# fixie18.net
KiCad netlist of a schematic drawn in EAGLE
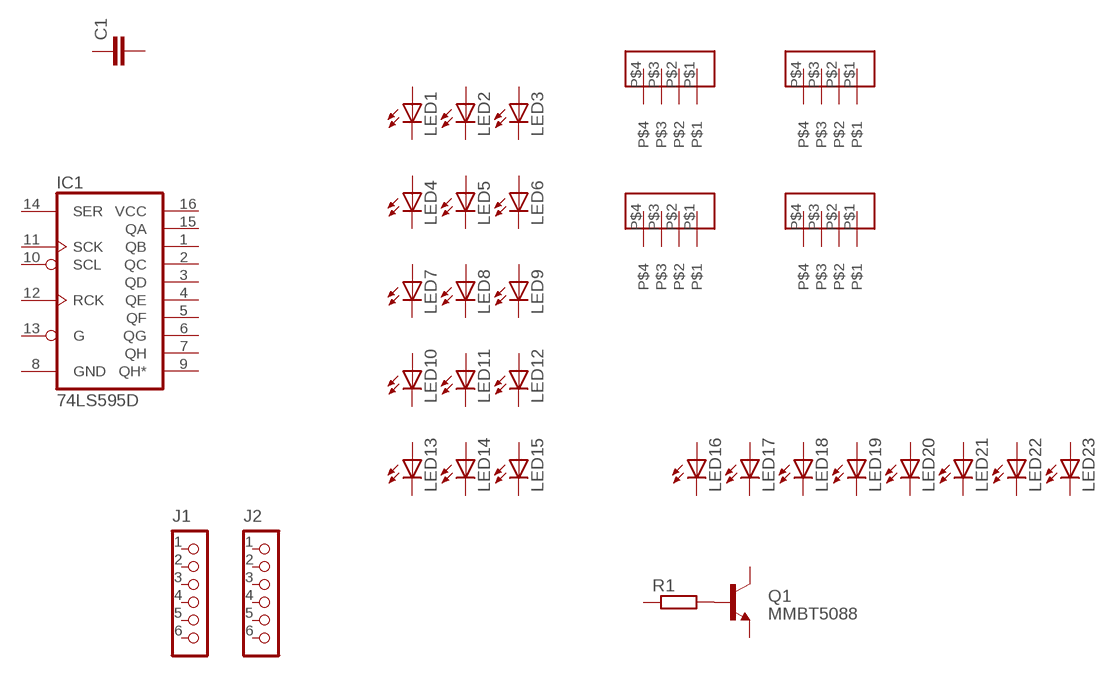
[diagram p0: schematic, sheet 1]

(export (version "E")
  (design (tool "Eeschema 10.0.6"))
  (components
    (comp (ref "C1")
      (value "C-EUC1206")
      (footprint "eagle-import:C1206")
      (libsource (lib "eagle-import") (part "C-EUC1206"))
    )
    (comp (ref "IC1")
      (value "74LS595D")
      (footprint "eagle-import:SO16")
      (libsource (lib "eagle-import") (part "74595DLS"))
    )
    (comp (ref "J1")
      (value "CON_HEADER_1X06-PTH")
      (footprint "eagle-import:M1X6")
      (libsource (lib "eagle-import") (part "CON_HEADER_1X06-PTH"))
    )
    (comp (ref "J2")
      (value "CON_HEADER_1X06-PTH")
      (footprint "eagle-import:M1X6")
      (libsource (lib "eagle-import") (part "CON_HEADER_1X06-PTH"))
    )
    (comp (ref "JP1")
      (value "HEADER_CENTERED_04")
      (footprint "eagle-import:HEADER_04_CENTERED")
      (libsource (lib "eagle-import") (part "HEADER_CENTERED_04"))
    )
    (comp (ref "JP2")
      (value "HEADER_CENTERED_04")
      (footprint "eagle-import:HEADER_04_CENTERED")
      (libsource (lib "eagle-import") (part "HEADER_CENTERED_04"))
    )
    (comp (ref "JP3")
      (value "HEADER_CENTERED_04")
      (footprint "eagle-import:HEADER_04_CENTERED")
      (libsource (lib "eagle-import") (part "HEADER_CENTERED_04"))
    )
    (comp (ref "JP4")
      (value "HEADER_CENTERED_04")
      (footprint "eagle-import:HEADER_04_CENTERED")
      (libsource (lib "eagle-import") (part "HEADER_CENTERED_04"))
    )
    (comp (ref "LED1")
      (value "LED3MM")
      (footprint "eagle-import:LED3MM")
      (libsource (lib "eagle-import") (part "LED3MM"))
    )
    (comp (ref "LED2")
      (value "LED3MM")
      (footprint "eagle-import:LED3MM")
      (libsource (lib "eagle-import") (part "LED3MM"))
    )
    (comp (ref "LED3")
      (value "LED3MM")
      (footprint "eagle-import:LED3MM")
      (libsource (lib "eagle-import") (part "LED3MM"))
    )
    (comp (ref "LED4")
      (value "LED3MM")
      (footprint "eagle-import:LED3MM")
      (libsource (lib "eagle-import") (part "LED3MM"))
    )
    (comp (ref "LED5")
      (value "LED3MM")
      (footprint "eagle-import:LED3MM")
      (libsource (lib "eagle-import") (part "LED3MM"))
    )
    (comp (ref "LED6")
      (value "LED3MM")
      (footprint "eagle-import:LED3MM")
      (libsource (lib "eagle-import") (part "LED3MM"))
    )
    (comp (ref "LED7")
      (value "LED3MM")
      (footprint "eagle-import:LED3MM")
      (libsource (lib "eagle-import") (part "LED3MM"))
    )
    (comp (ref "LED8")
      (value "LED3MM")
      (footprint "eagle-import:LED3MM")
      (libsource (lib "eagle-import") (part "LED3MM"))
    )
    (comp (ref "LED9")
      (value "LED3MM")
      (footprint "eagle-import:LED3MM")
      (libsource (lib "eagle-import") (part "LED3MM"))
    )
    (comp (ref "LED10")
      (value "LED3MM")
      (footprint "eagle-import:LED3MM")
      (libsource (lib "eagle-import") (part "LED3MM"))
    )
    (comp (ref "LED11")
      (value "LED3MM")
      (footprint "eagle-import:LED3MM")
      (libsource (lib "eagle-import") (part "LED3MM"))
    )
    (comp (ref "LED12")
      (value "LED3MM")
      (footprint "eagle-import:LED3MM")
      (libsource (lib "eagle-import") (part "LED3MM"))
    )
    (comp (ref "LED13")
      (value "LED3MM")
      (footprint "eagle-import:LED3MM")
      (libsource (lib "eagle-import") (part "LED3MM"))
    )
    (comp (ref "LED14")
      (value "LED3MM")
      (footprint "eagle-import:LED3MM")
      (libsource (lib "eagle-import") (part "LED3MM"))
    )
    (comp (ref "LED15")
      (value "LED3MM")
      (footprint "eagle-import:LED3MM")
      (libsource (lib "eagle-import") (part "LED3MM"))
    )
    (comp (ref "LED16")
      (value "LEDCHIPLED_1206")
      (footprint "eagle-import:CHIPLED_1206")
      (libsource (lib "eagle-import") (part "LEDCHIPLED_1206"))
    )
    (comp (ref "LED17")
      (value "LEDCHIPLED_1206")
      (footprint "eagle-import:CHIPLED_1206")
      (libsource (lib "eagle-import") (part "LEDCHIPLED_1206"))
    )
    (comp (ref "LED18")
      (value "LEDCHIPLED_1206")
      (footprint "eagle-import:CHIPLED_1206")
      (libsource (lib "eagle-import") (part "LEDCHIPLED_1206"))
    )
    (comp (ref "LED19")
      (value "LEDCHIPLED_1206")
      (footprint "eagle-import:CHIPLED_1206")
      (libsource (lib "eagle-import") (part "LEDCHIPLED_1206"))
    )
    (comp (ref "LED20")
      (value "LEDCHIPLED_1206")
      (footprint "eagle-import:CHIPLED_1206")
      (libsource (lib "eagle-import") (part "LEDCHIPLED_1206"))
    )
    (comp (ref "LED21")
      (value "LEDCHIPLED_1206")
      (footprint "eagle-import:CHIPLED_1206")
      (libsource (lib "eagle-import") (part "LEDCHIPLED_1206"))
    )
    (comp (ref "LED22")
      (value "LEDCHIPLED_1206")
      (footprint "eagle-import:CHIPLED_1206")
      (libsource (lib "eagle-import") (part "LEDCHIPLED_1206"))
    )
    (comp (ref "LED23")
      (value "LEDCHIPLED_1206")
      (footprint "eagle-import:CHIPLED_1206")
      (libsource (lib "eagle-import") (part "LEDCHIPLED_1206"))
    )
    (comp (ref "Q1")
      (value "MMBT5088")
      (footprint "eagle-import:SOT23")
      (libsource (lib "eagle-import") (part "TRANSISTOR_NPNMMBT5088"))
    )
    (comp (ref "R1")
      (value "R-EU_M1206")
      (footprint "eagle-import:M1206")
      (libsource (lib "eagle-import") (part "R-EU_M1206"))
    )
  )
  (nets
    (net (code "1") (name "/GND") (class "Default")
      (node (ref "IC1") (pin "8") (pinfunction "GND_8") (pintype "power_in"))
    )
    (net (code "2") (name "/VCC") (class "Default")
      (node (ref "IC1") (pin "16") (pinfunction "VCC_16") (pintype "power_in"))
    )
    (net (code "3") (name "Net-(Q1-B)") (class "Default")
      (node (ref "Q1") (pin "1") (pinfunction "B_1") (pintype "passive"))
      (node (ref "R1") (pin "2") (pinfunction "2_2") (pintype "passive"))
    )
    (net (code "4") (name "unconnected-(C1-Pad1)") (class "Default")
      (node (ref "C1") (pin "1") (pinfunction "1_1") (pintype "passive"))
    )
    (net (code "5") (name "unconnected-(C1-Pad2)") (class "Default")
      (node (ref "C1") (pin "2") (pinfunction "2_2") (pintype "passive"))
    )
    (net (code "6") (name "unconnected-(IC1-G-Pad13)") (class "Default")
      (node (ref "IC1") (pin "13") (pinfunction "G_13") (pintype "input"))
    )
    (net (code "7") (name "unconnected-(IC1-QA-Pad15)") (class "Default")
      (node (ref "IC1") (pin "15") (pinfunction "QA_15") (pintype "tri_state"))
    )
    (net (code "8") (name "unconnected-(IC1-QB-Pad1)") (class "Default")
      (node (ref "IC1") (pin "1") (pinfunction "QB_1") (pintype "tri_state"))
    )
    (net (code "9") (name "unconnected-(IC1-QC-Pad2)") (class "Default")
      (node (ref "IC1") (pin "2") (pinfunction "QC_2") (pintype "tri_state"))
    )
    (net (code "10") (name "unconnected-(IC1-QD-Pad3)") (class "Default")
      (node (ref "IC1") (pin "3") (pinfunction "QD_3") (pintype "tri_state"))
    )
    (net (code "11") (name "unconnected-(IC1-QE-Pad4)") (class "Default")
      (node (ref "IC1") (pin "4") (pinfunction "QE_4") (pintype "tri_state"))
    )
    (net (code "12") (name "unconnected-(IC1-QF-Pad5)") (class "Default")
      (node (ref "IC1") (pin "5") (pinfunction "QF_5") (pintype "tri_state"))
    )
    (net (code "13") (name "unconnected-(IC1-QG-Pad6)") (class "Default")
      (node (ref "IC1") (pin "6") (pinfunction "QG_6") (pintype "tri_state"))
    )
    (net (code "14") (name "unconnected-(IC1-QH*-Pad9)") (class "Default")
      (node (ref "IC1") (pin "9") (pinfunction "QH*_9") (pintype "tri_state"))
    )
    (net (code "15") (name "unconnected-(IC1-QH-Pad7)") (class "Default")
      (node (ref "IC1") (pin "7") (pinfunction "QH_7") (pintype "tri_state"))
    )
    (net (code "16") (name "unconnected-(IC1-RCK-Pad12)") (class "Default")
      (node (ref "IC1") (pin "12") (pinfunction "RCK_12") (pintype "input"))
    )
    (net (code "17") (name "unconnected-(IC1-SCK-Pad11)") (class "Default")
      (node (ref "IC1") (pin "11") (pinfunction "SCK_11") (pintype "input"))
    )
    (net (code "18") (name "unconnected-(IC1-SCL-Pad10)") (class "Default")
      (node (ref "IC1") (pin "10") (pinfunction "SCL_10") (pintype "input"))
    )
    (net (code "19") (name "unconnected-(IC1-SER-Pad14)") (class "Default")
      (node (ref "IC1") (pin "14") (pinfunction "SER_14") (pintype "input"))
    )
    (net (code "20") (name "unconnected-(J1-Pad1)") (class "Default")
      (node (ref "J1") (pin "1") (pinfunction "1_1") (pintype "bidirectional"))
    )
    (net (code "21") (name "unconnected-(J1-Pad2)") (class "Default")
      (node (ref "J1") (pin "2") (pinfunction "2_2") (pintype "bidirectional"))
    )
    (net (code "22") (name "unconnected-(J1-Pad3)") (class "Default")
      (node (ref "J1") (pin "3") (pinfunction "3_3") (pintype "passive"))
    )
    (net (code "23") (name "unconnected-(J1-Pad4)") (class "Default")
      (node (ref "J1") (pin "4") (pinfunction "4_4") (pintype "passive"))
    )
    (net (code "24") (name "unconnected-(J1-Pad5)") (class "Default")
      (node (ref "J1") (pin "5") (pinfunction "5_5") (pintype "passive"))
    )
    (net (code "25") (name "unconnected-(J1-Pad6)") (class "Default")
      (node (ref "J1") (pin "6") (pinfunction "6_6") (pintype "passive"))
    )
    (net (code "26") (name "unconnected-(J2-Pad1)") (class "Default")
      (node (ref "J2") (pin "1") (pinfunction "1_1") (pintype "bidirectional"))
    )
    (net (code "27") (name "unconnected-(J2-Pad2)") (class "Default")
      (node (ref "J2") (pin "2") (pinfunction "2_2") (pintype "bidirectional"))
    )
    (net (code "28") (name "unconnected-(J2-Pad3)") (class "Default")
      (node (ref "J2") (pin "3") (pinfunction "3_3") (pintype "passive"))
    )
    (net (code "29") (name "unconnected-(J2-Pad4)") (class "Default")
      (node (ref "J2") (pin "4") (pinfunction "4_4") (pintype "passive"))
    )
    (net (code "30") (name "unconnected-(J2-Pad5)") (class "Default")
      (node (ref "J2") (pin "5") (pinfunction "5_5") (pintype "passive"))
    )
    (net (code "31") (name "unconnected-(J2-Pad6)") (class "Default")
      (node (ref "J2") (pin "6") (pinfunction "6_6") (pintype "passive"))
    )
    (net (code "32") (name "unconnected-(JP1-PadP$1)") (class "Default")
      (node (ref "JP1") (pin "P$1") (pinfunction "P$1_P$1") (pintype "bidirectional"))
    )
    (net (code "33") (name "unconnected-(JP1-PadP$2)") (class "Default")
      (node (ref "JP1") (pin "P$2") (pinfunction "P$2_P$2") (pintype "bidirectional"))
    )
    (net (code "34") (name "unconnected-(JP1-PadP$3)") (class "Default")
      (node (ref "JP1") (pin "P$3") (pinfunction "P$3_P$3") (pintype "bidirectional"))
    )
    (net (code "35") (name "unconnected-(JP1-PadP$4)") (class "Default")
      (node (ref "JP1") (pin "P$4") (pinfunction "P$4_P$4") (pintype "bidirectional"))
    )
    (net (code "36") (name "unconnected-(JP2-PadP$1)") (class "Default")
      (node (ref "JP2") (pin "P$1") (pinfunction "P$1_P$1") (pintype "bidirectional"))
    )
    (net (code "37") (name "unconnected-(JP2-PadP$2)") (class "Default")
      (node (ref "JP2") (pin "P$2") (pinfunction "P$2_P$2") (pintype "bidirectional"))
    )
    (net (code "38") (name "unconnected-(JP2-PadP$3)") (class "Default")
      (node (ref "JP2") (pin "P$3") (pinfunction "P$3_P$3") (pintype "bidirectional"))
    )
    (net (code "39") (name "unconnected-(JP2-PadP$4)") (class "Default")
      (node (ref "JP2") (pin "P$4") (pinfunction "P$4_P$4") (pintype "bidirectional"))
    )
    (net (code "40") (name "unconnected-(JP3-PadP$1)") (class "Default")
      (node (ref "JP3") (pin "P$1") (pinfunction "P$1_P$1") (pintype "bidirectional"))
    )
    (net (code "41") (name "unconnected-(JP3-PadP$2)") (class "Default")
      (node (ref "JP3") (pin "P$2") (pinfunction "P$2_P$2") (pintype "bidirectional"))
    )
    (net (code "42") (name "unconnected-(JP3-PadP$3)") (class "Default")
      (node (ref "JP3") (pin "P$3") (pinfunction "P$3_P$3") (pintype "bidirectional"))
    )
    (net (code "43") (name "unconnected-(JP3-PadP$4)") (class "Default")
      (node (ref "JP3") (pin "P$4") (pinfunction "P$4_P$4") (pintype "bidirectional"))
    )
    (net (code "44") (name "unconnected-(JP4-PadP$1)") (class "Default")
      (node (ref "JP4") (pin "P$1") (pinfunction "P$1_P$1") (pintype "bidirectional"))
    )
    (net (code "45") (name "unconnected-(JP4-PadP$2)") (class "Default")
      (node (ref "JP4") (pin "P$2") (pinfunction "P$2_P$2") (pintype "bidirectional"))
    )
    (net (code "46") (name "unconnected-(JP4-PadP$3)") (class "Default")
      (node (ref "JP4") (pin "P$3") (pinfunction "P$3_P$3") (pintype "bidirectional"))
    )
    (net (code "47") (name "unconnected-(JP4-PadP$4)") (class "Default")
      (node (ref "JP4") (pin "P$4") (pinfunction "P$4_P$4") (pintype "bidirectional"))
    )
    (net (code "48") (name "unconnected-(LED1-C-PadK)") (class "Default")
      (node (ref "LED1") (pin "K") (pinfunction "C_K") (pintype "passive"))
    )
    (net (code "49") (name "unconnected-(LED1-PadA)") (class "Default")
      (node (ref "LED1") (pin "A") (pinfunction "A_A") (pintype "passive"))
    )
    (net (code "50") (name "unconnected-(LED2-C-PadK)") (class "Default")
      (node (ref "LED2") (pin "K") (pinfunction "C_K") (pintype "passive"))
    )
    (net (code "51") (name "unconnected-(LED2-PadA)") (class "Default")
      (node (ref "LED2") (pin "A") (pinfunction "A_A") (pintype "passive"))
    )
    (net (code "52") (name "unconnected-(LED3-C-PadK)") (class "Default")
      (node (ref "LED3") (pin "K") (pinfunction "C_K") (pintype "passive"))
    )
    (net (code "53") (name "unconnected-(LED3-PadA)") (class "Default")
      (node (ref "LED3") (pin "A") (pinfunction "A_A") (pintype "passive"))
    )
    (net (code "54") (name "unconnected-(LED4-C-PadK)") (class "Default")
      (node (ref "LED4") (pin "K") (pinfunction "C_K") (pintype "passive"))
    )
    (net (code "55") (name "unconnected-(LED4-PadA)") (class "Default")
      (node (ref "LED4") (pin "A") (pinfunction "A_A") (pintype "passive"))
    )
    (net (code "56") (name "unconnected-(LED5-C-PadK)") (class "Default")
      (node (ref "LED5") (pin "K") (pinfunction "C_K") (pintype "passive"))
    )
    (net (code "57") (name "unconnected-(LED5-PadA)") (class "Default")
      (node (ref "LED5") (pin "A") (pinfunction "A_A") (pintype "passive"))
    )
    (net (code "58") (name "unconnected-(LED6-C-PadK)") (class "Default")
      (node (ref "LED6") (pin "K") (pinfunction "C_K") (pintype "passive"))
    )
    (net (code "59") (name "unconnected-(LED6-PadA)") (class "Default")
      (node (ref "LED6") (pin "A") (pinfunction "A_A") (pintype "passive"))
    )
    (net (code "60") (name "unconnected-(LED7-C-PadK)") (class "Default")
      (node (ref "LED7") (pin "K") (pinfunction "C_K") (pintype "passive"))
    )
    (net (code "61") (name "unconnected-(LED7-PadA)") (class "Default")
      (node (ref "LED7") (pin "A") (pinfunction "A_A") (pintype "passive"))
    )
    (net (code "62") (name "unconnected-(LED8-C-PadK)") (class "Default")
      (node (ref "LED8") (pin "K") (pinfunction "C_K") (pintype "passive"))
    )
    (net (code "63") (name "unconnected-(LED8-PadA)") (class "Default")
      (node (ref "LED8") (pin "A") (pinfunction "A_A") (pintype "passive"))
    )
    (net (code "64") (name "unconnected-(LED9-C-PadK)") (class "Default")
      (node (ref "LED9") (pin "K") (pinfunction "C_K") (pintype "passive"))
    )
    (net (code "65") (name "unconnected-(LED9-PadA)") (class "Default")
      (node (ref "LED9") (pin "A") (pinfunction "A_A") (pintype "passive"))
    )
    (net (code "66") (name "unconnected-(LED10-C-PadK)") (class "Default")
      (node (ref "LED10") (pin "K") (pinfunction "C_K") (pintype "passive"))
    )
    (net (code "67") (name "unconnected-(LED10-PadA)") (class "Default")
      (node (ref "LED10") (pin "A") (pinfunction "A_A") (pintype "passive"))
    )
    (net (code "68") (name "unconnected-(LED11-C-PadK)") (class "Default")
      (node (ref "LED11") (pin "K") (pinfunction "C_K") (pintype "passive"))
    )
    (net (code "69") (name "unconnected-(LED11-PadA)") (class "Default")
      (node (ref "LED11") (pin "A") (pinfunction "A_A") (pintype "passive"))
    )
    (net (code "70") (name "unconnected-(LED12-C-PadK)") (class "Default")
      (node (ref "LED12") (pin "K") (pinfunction "C_K") (pintype "passive"))
    )
    (net (code "71") (name "unconnected-(LED12-PadA)") (class "Default")
      (node (ref "LED12") (pin "A") (pinfunction "A_A") (pintype "passive"))
    )
    (net (code "72") (name "unconnected-(LED13-C-PadK)") (class "Default")
      (node (ref "LED13") (pin "K") (pinfunction "C_K") (pintype "passive"))
    )
    (net (code "73") (name "unconnected-(LED13-PadA)") (class "Default")
      (node (ref "LED13") (pin "A") (pinfunction "A_A") (pintype "passive"))
    )
    (net (code "74") (name "unconnected-(LED14-C-PadK)") (class "Default")
      (node (ref "LED14") (pin "K") (pinfunction "C_K") (pintype "passive"))
    )
    (net (code "75") (name "unconnected-(LED14-PadA)") (class "Default")
      (node (ref "LED14") (pin "A") (pinfunction "A_A") (pintype "passive"))
    )
    (net (code "76") (name "unconnected-(LED15-C-PadK)") (class "Default")
      (node (ref "LED15") (pin "K") (pinfunction "C_K") (pintype "passive"))
    )
    (net (code "77") (name "unconnected-(LED15-PadA)") (class "Default")
      (node (ref "LED15") (pin "A") (pinfunction "A_A") (pintype "passive"))
    )
    (net (code "78") (name "unconnected-(LED16-PadA)") (class "Default")
      (node (ref "LED16") (pin "A") (pinfunction "A_A") (pintype "passive"))
    )
    (net (code "79") (name "unconnected-(LED16-PadC)") (class "Default")
      (node (ref "LED16") (pin "C") (pinfunction "C_C") (pintype "passive"))
    )
    (net (code "80") (name "unconnected-(LED17-PadA)") (class "Default")
      (node (ref "LED17") (pin "A") (pinfunction "A_A") (pintype "passive"))
    )
    (net (code "81") (name "unconnected-(LED17-PadC)") (class "Default")
      (node (ref "LED17") (pin "C") (pinfunction "C_C") (pintype "passive"))
    )
    (net (code "82") (name "unconnected-(LED18-PadA)") (class "Default")
      (node (ref "LED18") (pin "A") (pinfunction "A_A") (pintype "passive"))
    )
    (net (code "83") (name "unconnected-(LED18-PadC)") (class "Default")
      (node (ref "LED18") (pin "C") (pinfunction "C_C") (pintype "passive"))
    )
    (net (code "84") (name "unconnected-(LED19-PadA)") (class "Default")
      (node (ref "LED19") (pin "A") (pinfunction "A_A") (pintype "passive"))
    )
    (net (code "85") (name "unconnected-(LED19-PadC)") (class "Default")
      (node (ref "LED19") (pin "C") (pinfunction "C_C") (pintype "passive"))
    )
    (net (code "86") (name "unconnected-(LED20-PadA)") (class "Default")
      (node (ref "LED20") (pin "A") (pinfunction "A_A") (pintype "passive"))
    )
    (net (code "87") (name "unconnected-(LED20-PadC)") (class "Default")
      (node (ref "LED20") (pin "C") (pinfunction "C_C") (pintype "passive"))
    )
    (net (code "88") (name "unconnected-(LED21-PadA)") (class "Default")
      (node (ref "LED21") (pin "A") (pinfunction "A_A") (pintype "passive"))
    )
    (net (code "89") (name "unconnected-(LED21-PadC)") (class "Default")
      (node (ref "LED21") (pin "C") (pinfunction "C_C") (pintype "passive"))
    )
    (net (code "90") (name "unconnected-(LED22-PadA)") (class "Default")
      (node (ref "LED22") (pin "A") (pinfunction "A_A") (pintype "passive"))
    )
    (net (code "91") (name "unconnected-(LED22-PadC)") (class "Default")
      (node (ref "LED22") (pin "C") (pinfunction "C_C") (pintype "passive"))
    )
    (net (code "92") (name "unconnected-(LED23-PadA)") (class "Default")
      (node (ref "LED23") (pin "A") (pinfunction "A_A") (pintype "passive"))
    )
    (net (code "93") (name "unconnected-(LED23-PadC)") (class "Default")
      (node (ref "LED23") (pin "C") (pinfunction "C_C") (pintype "passive"))
    )
    (net (code "94") (name "unconnected-(Q1-C-Pad3)") (class "Default")
      (node (ref "Q1") (pin "3") (pinfunction "C_3") (pintype "passive"))
    )
    (net (code "95") (name "unconnected-(Q1-E-Pad2)") (class "Default")
      (node (ref "Q1") (pin "2") (pinfunction "E_2") (pintype "passive"))
    )
    (net (code "96") (name "unconnected-(R1-Pad1)") (class "Default")
      (node (ref "R1") (pin "1") (pinfunction "1_1") (pintype "passive"))
    )
  )
)
